# 2-LCD_CAMERA.net
KiCad netlist of a schematic drawn in Altium Designer
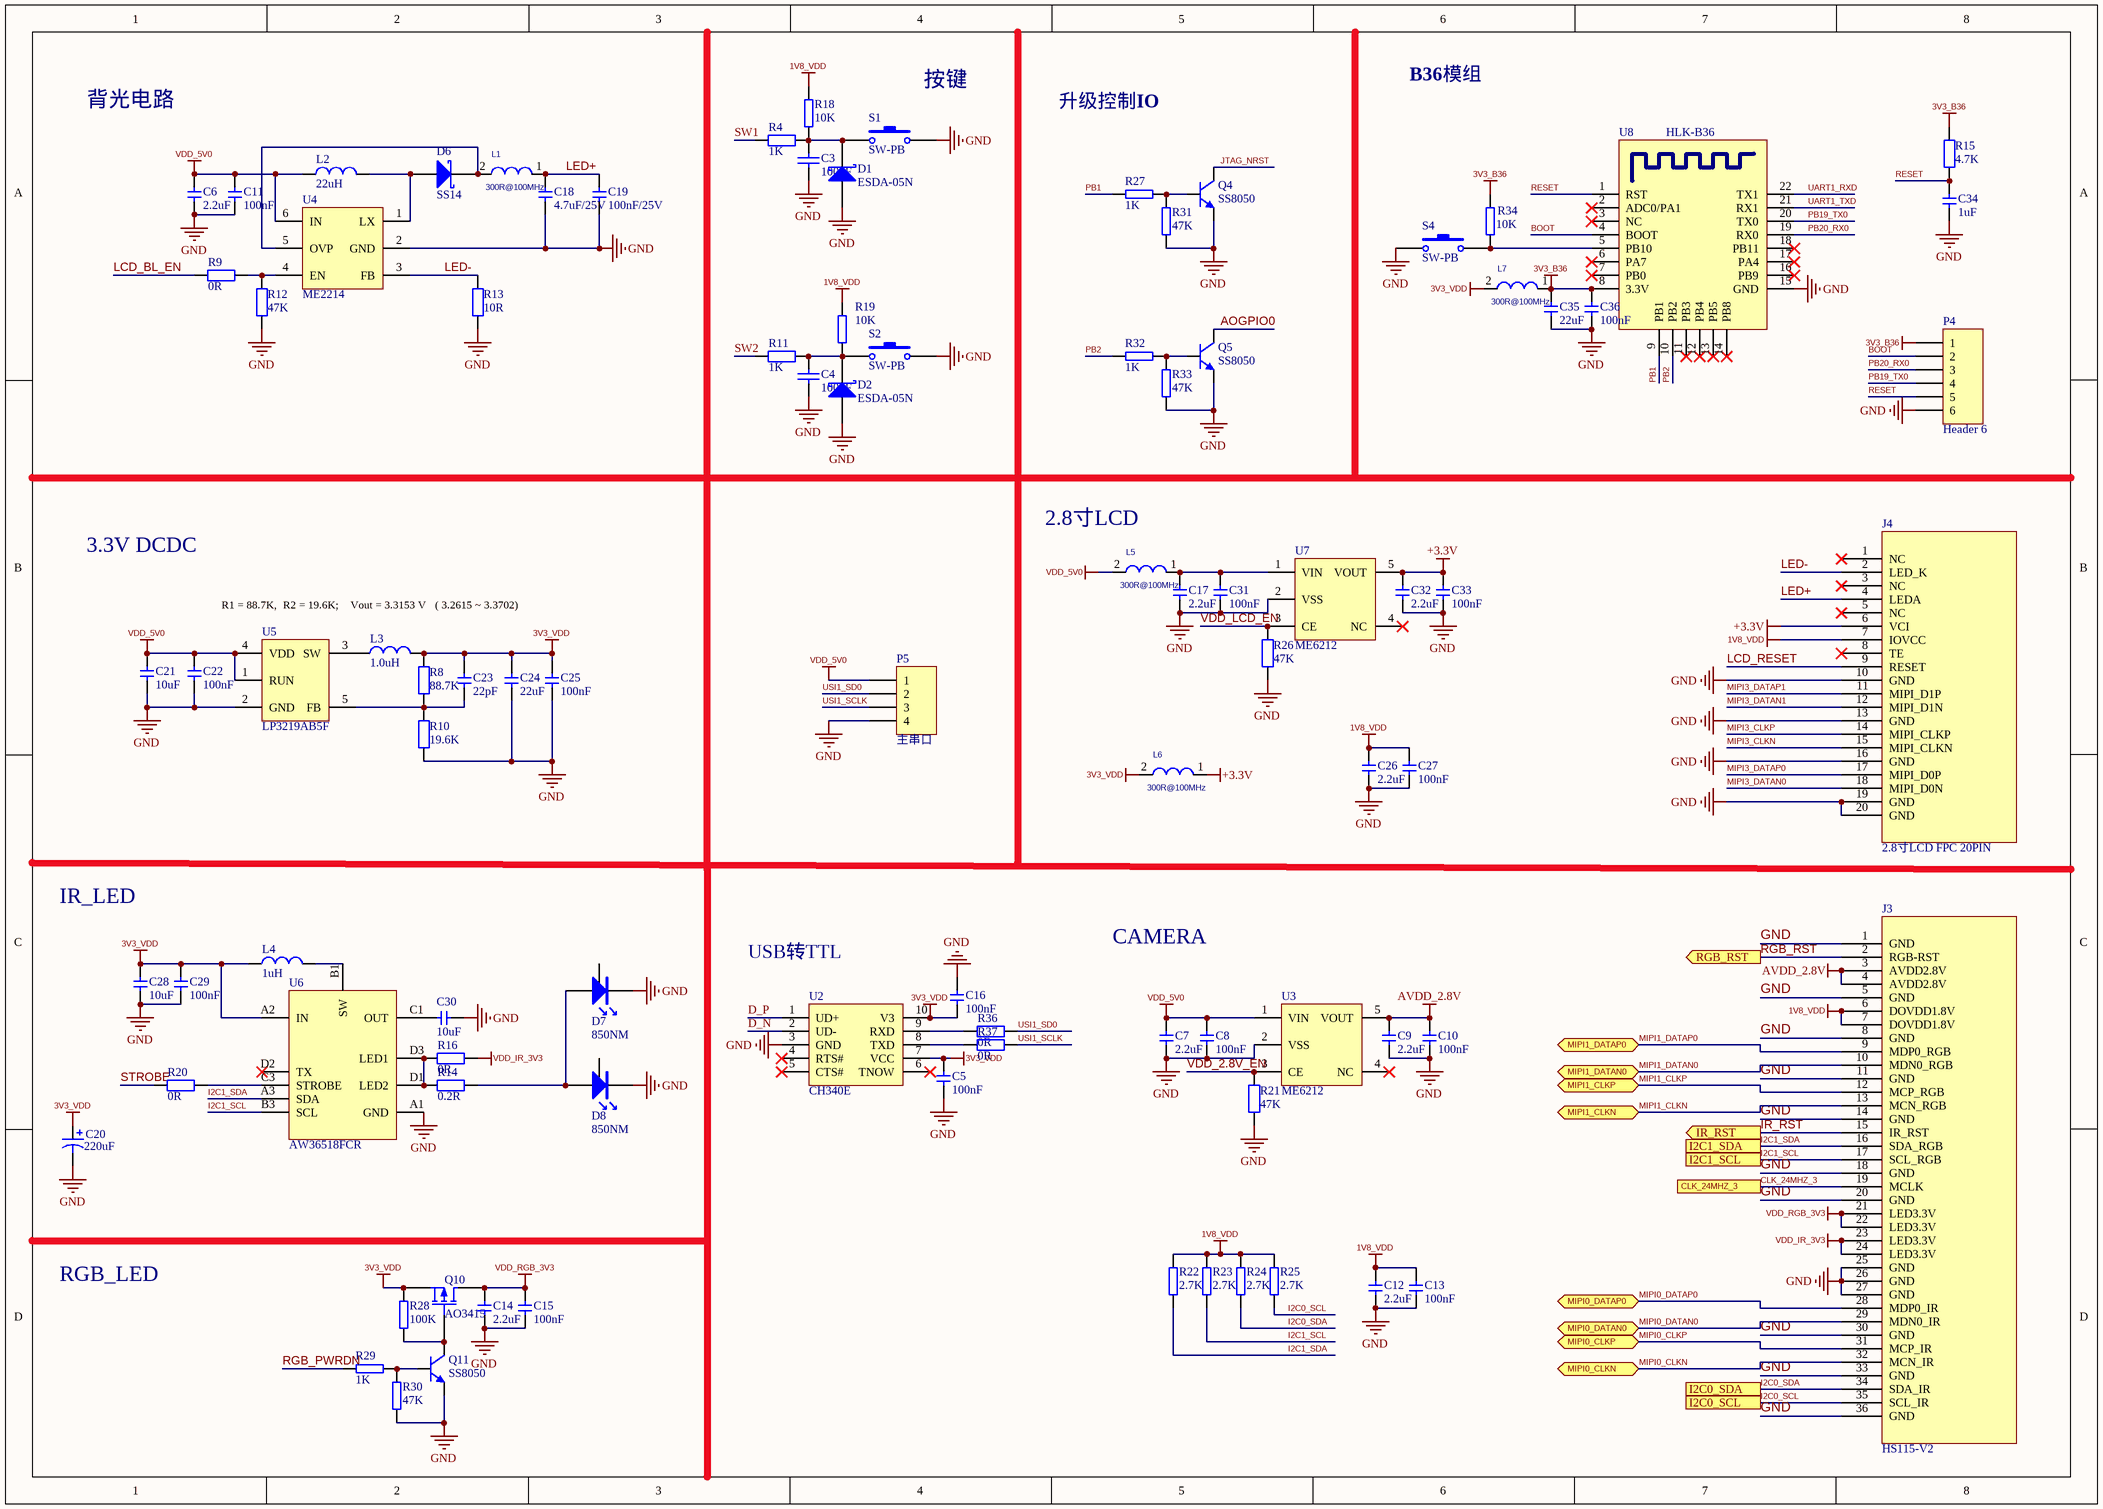
[diagram p0: 2-LCD&CAMERA.SchDoc]

(export (version "E")
  (design (tool "Eeschema 10.0.6"))
  (components
    (comp (ref "C3")
      (value "100nF")
      (footprint "C0402")
      (description "Capacitor")
      (libsource (lib "LORATEMPSENSOR_V0.02") (part "Cap"))
    )
    (comp (ref "C4")
      (value "100nF")
      (footprint "C0402")
      (description "Capacitor")
      (libsource (lib "LORATEMPSENSOR_V0.02") (part "Cap"))
    )
    (comp (ref "C5")
      (value "100nF")
      (footprint "C0402")
      (description "C?")
      (libsource (lib "HNCY_SCH_Lib") (part "CAP1"))
    )
    (comp (ref "C6")
      (value "2.2uF")
      (footprint "C0402")
      (description "C?")
      (libsource (lib "HNCY_SCH_Lib") (part "CAP1"))
    )
    (comp (ref "C7")
      (value "2.2uF")
      (footprint "C0402")
      (description "C?")
      (libsource (lib "HNCY_SCH_Lib") (part "CAP1"))
    )
    (comp (ref "C8")
      (value "100nF")
      (footprint "C0402")
      (description "C?")
      (libsource (lib "HNCY_SCH_Lib") (part "CAP1"))
    )
    (comp (ref "C9")
      (value "2.2uF")
      (footprint "C0402")
      (description "C?")
      (libsource (lib "HNCY_SCH_Lib") (part "CAP1"))
    )
    (comp (ref "C10")
      (value "100nF")
      (footprint "C0402")
      (description "C?")
      (libsource (lib "HNCY_SCH_Lib") (part "CAP1"))
    )
    (comp (ref "C11")
      (value "100nF")
      (footprint "C0402")
      (description "C?")
      (libsource (lib "HNCY_SCH_Lib") (part "CAP1"))
    )
    (comp (ref "C12")
      (value "2.2uF")
      (footprint "C0402")
      (description "C?")
      (libsource (lib "HNCY_SCH_Lib") (part "CAP1"))
    )
    (comp (ref "C13")
      (value "100nF")
      (footprint "C0402")
      (description "C?")
      (libsource (lib "HNCY_SCH_Lib") (part "CAP1"))
    )
    (comp (ref "C14")
      (value "2.2uF")
      (footprint "C0402")
      (description "C?")
      (libsource (lib "HNCY_SCH_Lib") (part "CAP1"))
    )
    (comp (ref "C15")
      (value "100nF")
      (footprint "C0402")
      (description "C?")
      (libsource (lib "HNCY_SCH_Lib") (part "CAP1"))
    )
    (comp (ref "C16")
      (value "100nF")
      (footprint "C0402")
      (description "C?")
      (libsource (lib "HNCY_SCH_Lib") (part "CAP1"))
    )
    (comp (ref "C17")
      (value "2.2uF")
      (footprint "C0402")
      (description "C?")
      (libsource (lib "HNCY_SCH_Lib") (part "CAP1"))
    )
    (comp (ref "C18")
      (value "4.7uF/25V")
      (footprint "Cap_0603")
      (description "C?")
      (libsource (lib "HNCY_SCH_Lib") (part "CAP1"))
    )
    (comp (ref "C19")
      (value "100nF/25V")
      (footprint "C0402")
      (description "C?")
      (libsource (lib "HNCY_SCH_Lib") (part "CAP1"))
    )
    (comp (ref "C20")
      (value "220uF")
      (footprint "SMD,6.3x7.7mm")
      (description "Polarized Capacitor (Radial)")
      (fields (field (name "Comment") "Cap Pol1") (field (name "PUBLISHER") "Altium Limited"))
      (libsource (lib "Miscellaneous Devices") (part "Cap Pol1"))
    )
    (comp (ref "C21")
      (value "10uF")
      (footprint "Cap_0603")
      (description "C?")
      (libsource (lib "HNCY_SCH_Lib") (part "CAP1"))
    )
    (comp (ref "C22")
      (value "100nF")
      (footprint "C0402")
      (description "C?")
      (libsource (lib "HNCY_SCH_Lib") (part "CAP1"))
    )
    (comp (ref "C23")
      (value "22pF")
      (footprint "C0402")
      (description "C?")
      (libsource (lib "HNCY_SCH_Lib") (part "CAP1"))
    )
    (comp (ref "C24")
      (value "22uF")
      (footprint "CAP_0603")
      (description "C?")
      (libsource (lib "HNCY_SCH_Lib") (part "CAP1"))
    )
    (comp (ref "C25")
      (value "100nF")
      (footprint "C0402")
      (description "C?")
      (libsource (lib "HNCY_SCH_Lib") (part "CAP1"))
    )
    (comp (ref "C26")
      (value "2.2uF")
      (footprint "C0402")
      (description "C?")
      (libsource (lib "HNCY_SCH_Lib") (part "CAP1"))
    )
    (comp (ref "C27")
      (value "100nF")
      (footprint "C0402")
      (description "C?")
      (libsource (lib "HNCY_SCH_Lib") (part "CAP1"))
    )
    (comp (ref "C28")
      (value "10uF")
      (footprint "C0402")
      (description "C?")
      (libsource (lib "HNCY_SCH_Lib") (part "CAP1"))
    )
    (comp (ref "C29")
      (value "100nF")
      (footprint "C0402")
      (description "C?")
      (libsource (lib "HNCY_SCH_Lib") (part "CAP1"))
    )
    (comp (ref "C30")
      (value "10uF")
      (footprint "C0402")
      (description "C?")
      (libsource (lib "HNCY_SCH_Lib") (part "CAP1"))
    )
    (comp (ref "C31")
      (value "100nF")
      (footprint "C0402")
      (description "C?")
      (libsource (lib "HNCY_SCH_Lib") (part "CAP1"))
    )
    (comp (ref "C32")
      (value "2.2uF")
      (footprint "C0402")
      (description "C?")
      (libsource (lib "HNCY_SCH_Lib") (part "CAP1"))
    )
    (comp (ref "C33")
      (value "100nF")
      (footprint "C0402")
      (description "C?")
      (libsource (lib "HNCY_SCH_Lib") (part "CAP1"))
    )
    (comp (ref "C34")
      (value "1uF")
      (footprint "C0402")
      (description "C?")
      (libsource (lib "HNCY_SCH_Lib") (part "CAP1"))
    )
    (comp (ref "C35")
      (value "22uF")
      (footprint "CAP_0603")
      (description "C?")
      (libsource (lib "HNCY_SCH_Lib") (part "CAP1"))
    )
    (comp (ref "C36")
      (value "100nF")
      (footprint "C0402")
      (description "C?")
      (libsource (lib "HNCY_SCH_Lib") (part "CAP1"))
    )
    (comp (ref "D1")
      (value "ESDA-05N")
      (footprint "R0402")
      (description "Silicon AF Schottky Diode for High-Speed Switching")
      (fields (field (name "PUBLISHER") "Altium Limited"))
      (libsource (lib "Miscellaneous Devices") (part "Diode BAS70"))
    )
    (comp (ref "D2")
      (value "ESDA-05N")
      (footprint "R0402")
      (description "Silicon AF Schottky Diode for High-Speed Switching")
      (fields (field (name "PUBLISHER") "Altium Limited"))
      (libsource (lib "Miscellaneous Devices") (part "Diode BAS70"))
    )
    (comp (ref "D6")
      (value "SS14")
      (footprint "SOD-123F")
      (description "Silicon AF Schottky Diode for High-Speed Switching")
      (fields (field (name "PUBLISHER") "Altium Limited"))
      (libsource (lib "Miscellaneous Devices") (part "Diode BAS70"))
    )
    (comp (ref "D7")
      (value "850NM")
      (footprint "LED-3535-850MM")
      (description "贴片LED，3535，红外850NM")
      (libsource (lib "MY SCHLIB") (part "LED_IR"))
    )
    (comp (ref "D8")
      (value "850NM")
      (footprint "LED-3535-850MM")
      (description "贴片LED，3535，红外850NM")
      (libsource (lib "Common") (part "LED_IR"))
    )
    (comp (ref "J3")
      (value "HS115-V2")
      (footprint "0.5-36PIN")
      (libsource (lib "MY SCHLIB") (part "HS115-V2"))
    )
    (comp (ref "J4")
      (value "2.8寸LCD FPC 20PIN")
      (footprint "0.5-20PIN-抽屉上接")
      (description "1-Lane MIPI")
      (libsource (lib "MY SCHLIB") (part "2.8寸LCD FPC 20PIN"))
    )
    (comp (ref "L1") (value "300R@100MHz") (footprint "Res_0603") (libsource (lib "*") (part "L/0402")))
    (comp (ref "L2") (value "22uH") (footprint "L3*3") (libsource (lib "封装") (part "LineInductors")))
    (comp (ref "L3")
      (value "1.0uH")
      (footprint "L2.5x2.0x1.0mm")
      (libsource (lib "封装") (part "LineInductors"))
    )
    (comp (ref "L4") (value "1uH") (footprint "L2.5x2.0x1.0mm") (libsource (lib "封装") (part "LineInductors")))
    (comp (ref "L5") (value "300R@100MHz") (footprint "Res_0603") (libsource (lib "*") (part "L/0402")))
    (comp (ref "L6") (value "300R@100MHz") (footprint "Res_0603") (libsource (lib "*") (part "L/0402")))
    (comp (ref "L7") (value "300R@100MHz") (footprint "Res_0603") (libsource (lib "*") (part "L/0402")))
    (comp (ref "P4")
      (value "Header 6")
      (footprint "HDR1X6")
      (description "Header, 6-Pin")
      (fields (field (name "PUBLISHER") "Altium Limited"))
      (libsource (lib "Miscellaneous Connectors") (part "Header 6"))
    )
    (comp (ref "P5")
      (value "主串口")
      (footprint "4P_2.5MM")
      (description "Header, 4-Pin")
      (fields (field (name "PUBLISHER") "Altium Limited"))
      (libsource (lib "Miscellaneous Connectors") (part "Header 4"))
    )
    (comp (ref "Q4")
      (value "SS8050")
      (footprint "SOT23-BEC")
      (description "贴片三极管")
      (libsource (lib "HNCY_SCH_Lib") (part "NPN"))
    )
    (comp (ref "Q5")
      (value "SS8050")
      (footprint "SOT23-BEC")
      (description "贴片三极管")
      (libsource (lib "HNCY_SCH_Lib") (part "NPN"))
    )
    (comp (ref "Q10") (value "AO3415") (footprint "SOT-23") (libsource (lib "*") (part "AO3415")))
    (comp (ref "Q11")
      (value "SS8050")
      (footprint "SOT23-BEC")
      (description "贴片三极管")
      (libsource (lib "HNCY_SCH_Lib") (part "NPN"))
    )
    (comp (ref "R4")
      (value "1K")
      (footprint "R0402")
      (description "Resistor")
      (fields (field (name "PUBLISHER") "Altium Limited"))
      (libsource (lib "") (part "Res2_1"))
    )
    (comp (ref "R8")
      (value "88.7K")
      (footprint "R0402")
      (description "Resistor")
      (fields (field (name "PUBLISHER") "Altium Limited"))
      (libsource (lib "Miscellaneous Devices") (part "Res2"))
    )
    (comp (ref "R9")
      (value "0R")
      (footprint "R0402")
      (description "Resistor")
      (fields (field (name "PUBLISHER") "Altium Limited"))
      (libsource (lib "") (part "Res2_1"))
    )
    (comp (ref "R10")
      (value "19.6K")
      (footprint "R0402")
      (description "Resistor")
      (fields (field (name "PUBLISHER") "Altium Limited"))
      (libsource (lib "") (part "Res2_3"))
    )
    (comp (ref "R11")
      (value "1K")
      (footprint "R0402")
      (description "Resistor")
      (fields (field (name "PUBLISHER") "Altium Limited"))
      (libsource (lib "") (part "Res2_1"))
    )
    (comp (ref "R12")
      (value "47K")
      (footprint "R0402")
      (description "Resistor")
      (fields (field (name "PUBLISHER") "Altium Limited"))
      (libsource (lib "Miscellaneous Devices") (part "Res2"))
    )
    (comp (ref "R13")
      (value "10R")
      (footprint "R0805")
      (description "Resistor")
      (fields (field (name "PUBLISHER") "Altium Limited"))
      (libsource (lib "") (part "Res2_3"))
    )
    (comp (ref "R14")
      (value "0.2R")
      (footprint "R0805")
      (description "Resistor")
      (fields (field (name "PUBLISHER") "Altium Limited"))
      (libsource (lib "") (part "Res2_1"))
    )
    (comp (ref "R15")
      (value "4.7K")
      (footprint "R0402")
      (description "Resistor")
      (fields (field (name "PUBLISHER") "Altium Limited"))
      (libsource (lib "") (part "Res2_3"))
    )
    (comp (ref "R16")
      (value "0R")
      (footprint "R0805")
      (description "Resistor")
      (fields (field (name "PUBLISHER") "Altium Limited"))
      (libsource (lib "") (part "Res2_1"))
    )
    (comp (ref "R18")
      (value "10K")
      (footprint "R0402")
      (description "R?")
      (libsource (lib "HNCY_SCH_Lib") (part "RES1"))
    )
    (comp (ref "R19")
      (value "10K")
      (footprint "R0402")
      (description "R?")
      (libsource (lib "HNCY_SCH_Lib") (part "RES1"))
    )
    (comp (ref "R20")
      (value "0R")
      (footprint "R0402")
      (description "Resistor")
      (fields (field (name "PUBLISHER") "Altium Limited"))
      (libsource (lib "") (part "Res2_1"))
    )
    (comp (ref "R21")
      (value "47K")
      (footprint "R0402")
      (description "Resistor")
      (fields (field (name "PUBLISHER") "Altium Limited"))
      (libsource (lib "Miscellaneous Devices") (part "Res2"))
    )
    (comp (ref "R22")
      (value "2.7K")
      (footprint "R0402")
      (description "R?")
      (libsource (lib "HNCY_SCH_Lib") (part "RES1"))
    )
    (comp (ref "R23")
      (value "2.7K")
      (footprint "R0402")
      (description "R?")
      (libsource (lib "HNCY_SCH_Lib") (part "RES1"))
    )
    (comp (ref "R24")
      (value "2.7K")
      (footprint "R0402")
      (description "R?")
      (libsource (lib "HNCY_SCH_Lib") (part "RES1"))
    )
    (comp (ref "R25")
      (value "2.7K")
      (footprint "R0402")
      (description "R?")
      (libsource (lib "HNCY_SCH_Lib") (part "RES1"))
    )
    (comp (ref "R26")
      (value "47K")
      (footprint "R0402")
      (description "Resistor")
      (fields (field (name "PUBLISHER") "Altium Limited"))
      (libsource (lib "Miscellaneous Devices") (part "Res2"))
    )
    (comp (ref "R27")
      (value "1K")
      (footprint "R0402")
      (description "R?")
      (libsource (lib "HNCY_SCH_Lib") (part "RES1"))
    )
    (comp (ref "R28")
      (value "100K")
      (footprint "R0402")
      (description "R?")
      (libsource (lib "HNCY_SCH_Lib") (part "RES1"))
    )
    (comp (ref "R29")
      (value "1K")
      (footprint "R0402")
      (description "R?")
      (libsource (lib "HNCY_SCH_Lib") (part "RES1"))
    )
    (comp (ref "R30")
      (value "47K")
      (footprint "R0402")
      (description "R?")
      (libsource (lib "HNCY_SCH_Lib") (part "RES1"))
    )
    (comp (ref "R31")
      (value "47K")
      (footprint "R0402")
      (description "R?")
      (libsource (lib "HNCY_SCH_Lib") (part "RES1"))
    )
    (comp (ref "R32")
      (value "1K")
      (footprint "R0402")
      (description "R?")
      (libsource (lib "HNCY_SCH_Lib") (part "RES1"))
    )
    (comp (ref "R33")
      (value "47K")
      (footprint "R0402")
      (description "R?")
      (libsource (lib "HNCY_SCH_Lib") (part "RES1"))
    )
    (comp (ref "R34")
      (value "10K")
      (footprint "R0402")
      (description "R?")
      (libsource (lib "HNCY_SCH_Lib") (part "RES1"))
    )
    (comp (ref "R36")
      (value "0R")
      (footprint "R0402")
      (description "Resistor")
      (fields (field (name "PUBLISHER") "Altium Limited"))
      (libsource (lib "") (part "Res2_2"))
    )
    (comp (ref "R37")
      (value "0R")
      (footprint "R0402")
      (description "Resistor")
      (fields (field (name "PUBLISHER") "Altium Limited"))
      (libsource (lib "") (part "Res2_2"))
    )
    (comp (ref "S1")
      (value "SW-PB")
      (footprint "轻触开关4.5x4.5")
      (description "Switch")
      (fields (field (name "PUBLISHER") "Altium Limited"))
      (libsource (lib "Miscellaneous Devices") (part "SW-PB"))
    )
    (comp (ref "S2")
      (value "SW-PB")
      (footprint "轻触开关4.5x4.5")
      (description "Switch")
      (fields (field (name "PUBLISHER") "Altium Limited"))
      (libsource (lib "Miscellaneous Devices") (part "SW-PB"))
    )
    (comp (ref "S4")
      (value "SW-PB")
      (footprint "轻触开关4.5x4.5")
      (description "Switch")
      (fields (field (name "PUBLISHER") "Altium Limited"))
      (libsource (lib "Miscellaneous Devices") (part "SW-PB"))
    )
    (comp (ref "U2") (value "CH340E") (footprint "MSOP-10") (libsource (lib "MY SCHLIB") (part "CH340E")))
    (comp (ref "U3") (value "ME6212") (footprint "SOT23-5") (libsource (lib "MY SCHLIB") (part "ME6212")))
    (comp (ref "U4") (value "ME2214") (footprint "SOT26") (libsource (lib "MY SCHLIB") (part "ME2214")))
    (comp (ref "U5") (value "LP3219AB5F") (footprint "SOT23-5") (libsource (lib "MY SCHLIB") (part "TD6817")))
    (comp (ref "U6")
      (value "AW36518FCR")
      (footprint "FCQFN-10L")
      (libsource (lib "MY SCHLIB") (part "AW36518FCR"))
    )
    (comp (ref "U7") (value "ME6212") (footprint "SOT23-5") (libsource (lib "MY SCHLIB") (part "ME6212")))
    (comp (ref "U8") (value "HLK-B36") (footprint "HLK-B36") (libsource (lib "MY SCHLIB") (part "HLK-B36")))
  )
  (nets
    (net (code "1") (name "+3.3V") (class "Default")
      (node (ref "C32") (pin "1") (pintype "passive"))
      (node (ref "C33") (pin "1") (pintype "passive"))
      (node (ref "J4") (pin "6") (pinfunction "VCI_6") (pintype "passive"))
      (node (ref "L6") (pin "1") (pinfunction "1_1") (pintype "passive"))
      (node (ref "U7") (pin "5") (pinfunction "VOUT_5") (pintype "passive"))
    )
    (net (code "2") (name "/AOGPIO0") (class "Default")
      (node (ref "Q5") (pin "C") (pinfunction "C_C") (pintype "passive"))
    )
    (net (code "3") (name "/BOOT") (class "Default")
      (node (ref "P4") (pin "2") (pinfunction "2_2") (pintype "passive"))
      (node (ref "U8") (pin "4") (pinfunction "BOOT_4") (pintype "passive"))
    )
    (net (code "4") (name "/CLK_24MHZ_3") (class "Default")
      (node (ref "J3") (pin "19") (pinfunction "MCLK_19") (pintype "passive"))
    )
    (net (code "5") (name "/D_N") (class "Default")
      (node (ref "U2") (pin "2") (pinfunction "UD-_2") (pintype "passive"))
    )
    (net (code "6") (name "/D_P") (class "Default")
      (node (ref "U2") (pin "1") (pinfunction "UD+_1") (pintype "passive"))
    )
    (net (code "7") (name "/I2C0_SCL") (class "Default")
      (node (ref "J3") (pin "35") (pinfunction "SCL_IR_35") (pintype "passive"))
      (node (ref "R25") (pin "2") (pinfunction "2_2") (pintype "passive"))
    )
    (net (code "8") (name "/I2C0_SDA") (class "Default")
      (node (ref "J3") (pin "34") (pinfunction "SDA_IR_34") (pintype "passive"))
      (node (ref "R24") (pin "2") (pinfunction "2_2") (pintype "passive"))
    )
    (net (code "9") (name "/I2C1_SCL") (class "Default")
      (node (ref "J3") (pin "17") (pinfunction "SCL_RGB_17") (pintype "passive"))
      (node (ref "R23") (pin "2") (pinfunction "2_2") (pintype "passive"))
      (node (ref "U6") (pin "B3") (pinfunction "SCL_B3") (pintype "passive"))
    )
    (net (code "10") (name "/I2C1_SDA") (class "Default")
      (node (ref "J3") (pin "16") (pinfunction "SDA_RGB_16") (pintype "passive"))
      (node (ref "R22") (pin "2") (pinfunction "2_2") (pintype "passive"))
      (node (ref "U6") (pin "A3") (pinfunction "SDA_A3") (pintype "passive"))
    )
    (net (code "11") (name "/IR_RST") (class "Default")
      (node (ref "J3") (pin "15") (pinfunction "IR_RST_15") (pintype "passive"))
    )
    (net (code "12") (name "/JTAG_NRST") (class "Default")
      (node (ref "Q4") (pin "C") (pinfunction "C_C") (pintype "passive"))
    )
    (net (code "13") (name "/LCD_BL_EN") (class "Default")
      (node (ref "R9") (pin "1") (pinfunction "1_1") (pintype "passive"))
    )
    (net (code "14") (name "/LCD_RESET") (class "Default")
      (node (ref "J4") (pin "9") (pinfunction "RESET_9") (pintype "passive"))
    )
    (net (code "15") (name "/LED+") (class "Default")
      (node (ref "C18") (pin "1") (pintype "passive"))
      (node (ref "C19") (pin "1") (pintype "passive"))
      (node (ref "J4") (pin "4") (pinfunction "LEDA_4") (pintype "passive"))
      (node (ref "L1") (pin "1") (pinfunction "1_1") (pintype "passive"))
    )
    (net (code "16") (name "/LED-") (class "Default")
      (node (ref "J4") (pin "2") (pinfunction "LED_K_2") (pintype "passive"))
      (node (ref "R13") (pin "1") (pinfunction "1_1") (pintype "passive"))
      (node (ref "U4") (pin "3") (pinfunction "FB_3") (pintype "passive"))
    )
    (net (code "17") (name "/MIPI0_CLKN") (class "Default")
      (node (ref "J3") (pin "32") (pinfunction "MCN_IR_32") (pintype "passive"))
    )
    (net (code "18") (name "/MIPI0_CLKP") (class "Default")
      (node (ref "J3") (pin "31") (pinfunction "MCP_IR_31") (pintype "passive"))
    )
    (net (code "19") (name "/MIPI0_DATAN0") (class "Default")
      (node (ref "J3") (pin "29") (pinfunction "MDN0_IR_29") (pintype "passive"))
    )
    (net (code "20") (name "/MIPI0_DATAP0") (class "Default")
      (node (ref "J3") (pin "28") (pinfunction "MDP0_IR_28") (pintype "passive"))
    )
    (net (code "21") (name "/MIPI1_CLKN") (class "Default")
      (node (ref "J3") (pin "13") (pinfunction "MCN_RGB_13") (pintype "passive"))
    )
    (net (code "22") (name "/MIPI1_CLKP") (class "Default")
      (node (ref "J3") (pin "12") (pinfunction "MCP_RGB_12") (pintype "passive"))
    )
    (net (code "23") (name "/MIPI1_DATAN0") (class "Default")
      (node (ref "J3") (pin "10") (pinfunction "MDN0_RGB_10") (pintype "passive"))
    )
    (net (code "24") (name "/MIPI1_DATAP0") (class "Default")
      (node (ref "J3") (pin "9") (pinfunction "MDP0_RGB_9") (pintype "passive"))
    )
    (net (code "25") (name "/MIPI3_CLKN") (class "Default")
      (node (ref "J4") (pin "15") (pinfunction "MIPI_CLKN_15") (pintype "passive"))
    )
    (net (code "26") (name "/MIPI3_CLKP") (class "Default")
      (node (ref "J4") (pin "14") (pinfunction "MIPI_CLKP_14") (pintype "passive"))
    )
    (net (code "27") (name "/MIPI3_DATAN0") (class "Default")
      (node (ref "J4") (pin "18") (pinfunction "MIPI_D0N_18") (pintype "passive"))
    )
    (net (code "28") (name "/MIPI3_DATAN1") (class "Default")
      (node (ref "J4") (pin "12") (pinfunction "MIPI_D1N_12") (pintype "passive"))
    )
    (net (code "29") (name "/MIPI3_DATAP0") (class "Default")
      (node (ref "J4") (pin "17") (pinfunction "MIPI_D0P_17") (pintype "passive"))
    )
    (net (code "30") (name "/MIPI3_DATAP1") (class "Default")
      (node (ref "J4") (pin "11") (pinfunction "MIPI_D1P_11") (pintype "passive"))
    )
    (net (code "31") (name "/PB1") (class "Default")
      (node (ref "R27") (pin "2") (pinfunction "2_2") (pintype "passive"))
      (node (ref "U8") (pin "9") (pinfunction "PB1_9") (pintype "passive"))
    )
    (net (code "32") (name "/PB2") (class "Default")
      (node (ref "R32") (pin "2") (pinfunction "2_2") (pintype "passive"))
      (node (ref "U8") (pin "10") (pinfunction "PB2_10") (pintype "passive"))
    )
    (net (code "33") (name "/PB19_TX0") (class "Default")
      (node (ref "P4") (pin "4") (pinfunction "4_4") (pintype "passive"))
      (node (ref "U8") (pin "20") (pinfunction "TX0_20") (pintype "passive"))
    )
    (net (code "34") (name "/PB20_RX0") (class "Default")
      (node (ref "P4") (pin "3") (pinfunction "3_3") (pintype "passive"))
      (node (ref "U8") (pin "19") (pinfunction "RX0_19") (pintype "passive"))
    )
    (net (code "35") (name "/RESET") (class "Default")
      (node (ref "C34") (pin "1") (pintype "passive"))
      (node (ref "P4") (pin "5") (pinfunction "5_5") (pintype "passive"))
      (node (ref "R15") (pin "2") (pinfunction "2_2") (pintype "passive"))
      (node (ref "U8") (pin "1") (pinfunction "RST_1") (pintype "passive"))
    )
    (net (code "36") (name "/RGB_PWRDN") (class "Default")
      (node (ref "R29") (pin "2") (pinfunction "2_2") (pintype "passive"))
    )
    (net (code "37") (name "/RGB_RST") (class "Default")
      (node (ref "J3") (pin "2") (pinfunction "RGB-RST_2") (pintype "passive"))
    )
    (net (code "38") (name "/STROBE") (class "Default")
      (node (ref "R20") (pin "1") (pinfunction "1_1") (pintype "passive"))
    )
    (net (code "39") (name "/SW1") (class "Default")
      (node (ref "R4") (pin "1") (pinfunction "1_1") (pintype "passive"))
    )
    (net (code "40") (name "/SW2") (class "Default")
      (node (ref "R11") (pin "1") (pinfunction "1_1") (pintype "passive"))
    )
    (net (code "41") (name "/UART1_RXD") (class "Default")
      (node (ref "U8") (pin "22") (pinfunction "TX1_22") (pintype "passive"))
    )
    (net (code "42") (name "/UART1_TXD") (class "Default")
      (node (ref "U8") (pin "21") (pinfunction "RX1_21") (pintype "passive"))
    )
    (net (code "43") (name "/USI1_SCLK") (class "Default")
      (node (ref "P5") (pin "3") (pinfunction "3_3") (pintype "passive"))
      (node (ref "R37") (pin "1") (pinfunction "1_1") (pintype "passive"))
    )
    (net (code "44") (name "/USI1_SD0") (class "Default")
      (node (ref "P5") (pin "2") (pinfunction "2_2") (pintype "passive"))
      (node (ref "R36") (pin "1") (pinfunction "1_1") (pintype "passive"))
    )
    (net (code "45") (name "/VDD_2.8V_EN") (class "Default")
      (node (ref "R21") (pin "2") (pinfunction "2_2") (pintype "passive"))
      (node (ref "U3") (pin "3") (pinfunction "CE_3") (pintype "passive"))
    )
    (net (code "46") (name "/VDD_LCD_EN") (class "Default")
      (node (ref "R26") (pin "2") (pinfunction "2_2") (pintype "passive"))
      (node (ref "U7") (pin "3") (pinfunction "CE_3") (pintype "passive"))
    )
    (net (code "47") (name "1V8_VDD") (class "Default")
      (node (ref "C12") (pin "1") (pintype "passive"))
      (node (ref "C13") (pin "1") (pintype "passive"))
      (node (ref "C26") (pin "1") (pintype "passive"))
      (node (ref "C27") (pin "1") (pintype "passive"))
      (node (ref "J3") (pin "6") (pinfunction "DOVDD1.8V_6") (pintype "passive"))
      (node (ref "J3") (pin "7") (pinfunction "DOVDD1.8V_7") (pintype "passive"))
      (node (ref "J4") (pin "7") (pinfunction "IOVCC_7") (pintype "passive"))
      (node (ref "R18") (pin "2") (pinfunction "2_2") (pintype "passive"))
      (node (ref "R19") (pin "2") (pinfunction "2_2") (pintype "passive"))
      (node (ref "R22") (pin "1") (pinfunction "1_1") (pintype "passive"))
      (node (ref "R23") (pin "1") (pinfunction "1_1") (pintype "passive"))
      (node (ref "R24") (pin "1") (pinfunction "1_1") (pintype "passive"))
      (node (ref "R25") (pin "1") (pinfunction "1_1") (pintype "passive"))
    )
    (net (code "48") (name "3V3_B36") (class "Default")
      (node (ref "C35") (pin "1") (pintype "passive"))
      (node (ref "C36") (pin "1") (pintype "passive"))
      (node (ref "L7") (pin "1") (pinfunction "1_1") (pintype "passive"))
      (node (ref "P4") (pin "1") (pinfunction "1_1") (pintype "passive"))
      (node (ref "R15") (pin "1") (pinfunction "1_1") (pintype "passive"))
      (node (ref "R34") (pin "2") (pinfunction "2_2") (pintype "passive"))
      (node (ref "U8") (pin "8") (pinfunction "3.3V_8") (pintype "passive"))
    )
    (net (code "49") (name "3V3_VDD") (class "Default")
      (node (ref "C16") (pin "1") (pintype "passive"))
      (node (ref "C20") (pin "1") (pinfunction "1_1") (pintype "passive"))
      (node (ref "C23") (pin "2") (pintype "passive"))
      (node (ref "C24") (pin "1") (pintype "passive"))
      (node (ref "C25") (pin "1") (pintype "passive"))
      (node (ref "C28") (pin "1") (pintype "passive"))
      (node (ref "C29") (pin "1") (pintype "passive"))
      (node (ref "C5") (pin "2") (pintype "passive"))
      (node (ref "L3") (pin "2") (pinfunction "2_2") (pintype "passive"))
      (node (ref "L4") (pin "1") (pinfunction "1_1") (pintype "passive"))
      (node (ref "L6") (pin "2") (pinfunction "2_2") (pintype "passive"))
      (node (ref "L7") (pin "2") (pinfunction "2_2") (pintype "passive"))
      (node (ref "Q10") (pin "2") (pinfunction "S_2") (pintype "passive"))
      (node (ref "R28") (pin "2") (pinfunction "2_2") (pintype "passive"))
      (node (ref "R8") (pin "2") (pinfunction "2_2") (pintype "passive"))
      (node (ref "U2") (pin "10") (pinfunction "V3_10") (pintype "passive"))
      (node (ref "U2") (pin "7") (pinfunction "VCC_7") (pintype "passive"))
      (node (ref "U6") (pin "A2") (pinfunction "IN_A2") (pintype "passive"))
    )
    (net (code "50") (name "AVDD_2.8V") (class "Default")
      (node (ref "C10") (pin "1") (pintype "passive"))
      (node (ref "C9") (pin "1") (pintype "passive"))
      (node (ref "J3") (pin "3") (pinfunction "AVDD2.8V_3") (pintype "passive"))
      (node (ref "J3") (pin "4") (pinfunction "AVDD2.8V_4") (pintype "passive"))
      (node (ref "U3") (pin "5") (pinfunction "VOUT_5") (pintype "passive"))
    )
    (net (code "51") (name "GND") (class "Default")
      (node (ref "C10") (pin "2") (pintype "passive"))
      (node (ref "C11") (pin "2") (pintype "passive"))
      (node (ref "C12") (pin "2") (pintype "passive"))
      (node (ref "C13") (pin "2") (pintype "passive"))
      (node (ref "C14") (pin "2") (pintype "passive"))
      (node (ref "C15") (pin "2") (pintype "passive"))
      (node (ref "C16") (pin "2") (pintype "passive"))
      (node (ref "C17") (pin "2") (pintype "passive"))
      (node (ref "C18") (pin "2") (pintype "passive"))
      (node (ref "C19") (pin "2") (pintype "passive"))
      (node (ref "C20") (pin "2") (pinfunction "2_2") (pintype "passive"))
      (node (ref "C21") (pin "2") (pintype "passive"))
      (node (ref "C22") (pin "2") (pintype "passive"))
      (node (ref "C24") (pin "2") (pintype "passive"))
      (node (ref "C25") (pin "2") (pintype "passive"))
      (node (ref "C26") (pin "2") (pintype "passive"))
      (node (ref "C27") (pin "2") (pintype "passive"))
      (node (ref "C28") (pin "2") (pintype "passive"))
      (node (ref "C29") (pin "2") (pintype "passive"))
      (node (ref "C3") (pin "2") (pinfunction "2_2") (pintype "passive"))
      (node (ref "C30") (pin "2") (pintype "passive"))
      (node (ref "C31") (pin "2") (pintype "passive"))
      (node (ref "C32") (pin "2") (pintype "passive"))
      (node (ref "C33") (pin "2") (pintype "passive"))
      (node (ref "C34") (pin "2") (pintype "passive"))
      (node (ref "C35") (pin "2") (pintype "passive"))
      (node (ref "C36") (pin "2") (pintype "passive"))
      (node (ref "C4") (pin "2") (pinfunction "2_2") (pintype "passive"))
      (node (ref "C5") (pin "1") (pintype "passive"))
      (node (ref "C6") (pin "2") (pintype "passive"))
      (node (ref "C7") (pin "2") (pintype "passive"))
      (node (ref "C8") (pin "2") (pintype "passive"))
      (node (ref "C9") (pin "2") (pintype "passive"))
      (node (ref "D1") (pin "1") (pinfunction "A_1") (pintype "passive"))
      (node (ref "D2") (pin "1") (pinfunction "A_1") (pintype "passive"))
      (node (ref "D7") (pin "K") (pinfunction "K_K") (pintype "passive"))
      (node (ref "D8") (pin "K") (pinfunction "K_K") (pintype "passive"))
      (node (ref "J3") (pin "1") (pinfunction "GND_1") (pintype "passive"))
      (node (ref "J3") (pin "11") (pinfunction "GND_11") (pintype "passive"))
      (node (ref "J3") (pin "14") (pinfunction "GND_14") (pintype "passive"))
      (node (ref "J3") (pin "18") (pinfunction "GND_18") (pintype "passive"))
      (node (ref "J3") (pin "20") (pinfunction "GND_20") (pintype "passive"))
      (node (ref "J3") (pin "25") (pinfunction "GND_25") (pintype "passive"))
      (node (ref "J3") (pin "26") (pinfunction "GND_26") (pintype "passive"))
      (node (ref "J3") (pin "27") (pinfunction "GND_27") (pintype "passive"))
      (node (ref "J3") (pin "30") (pinfunction "GND_30") (pintype "passive"))
      (node (ref "J3") (pin "33") (pinfunction "GND_33") (pintype "passive"))
      (node (ref "J3") (pin "36") (pinfunction "GND_36") (pintype "passive"))
      (node (ref "J3") (pin "5") (pinfunction "GND_5") (pintype "passive"))
      (node (ref "J3") (pin "8") (pinfunction "GND_8") (pintype "passive"))
      (node (ref "J4") (pin "10") (pinfunction "GND_10") (pintype "passive"))
      (node (ref "J4") (pin "13") (pinfunction "GND_13") (pintype "passive"))
      (node (ref "J4") (pin "16") (pinfunction "GND_16") (pintype "passive"))
      (node (ref "J4") (pin "19") (pinfunction "GND_19") (pintype "passive"))
      (node (ref "J4") (pin "20") (pinfunction "GND_20") (pintype "passive"))
      (node (ref "P4") (pin "6") (pinfunction "6_6") (pintype "passive"))
      (node (ref "P5") (pin "4") (pinfunction "4_4") (pintype "passive"))
      (node (ref "Q11") (pin "E") (pinfunction "E_E") (pintype "passive"))
      (node (ref "Q4") (pin "E") (pinfunction "E_E") (pintype "passive"))
      (node (ref "Q5") (pin "E") (pinfunction "E_E") (pintype "passive"))
      (node (ref "R10") (pin "2") (pinfunction "2_2") (pintype "passive"))
      (node (ref "R12") (pin "1") (pinfunction "1_1") (pintype "passive"))
      (node (ref "R13") (pin "2") (pinfunction "2_2") (pintype "passive"))
      (node (ref "R21") (pin "1") (pinfunction "1_1") (pintype "passive"))
      (node (ref "R26") (pin "1") (pinfunction "1_1") (pintype "passive"))
      (node (ref "R30") (pin "2") (pinfunction "2_2") (pintype "passive"))
      (node (ref "R31") (pin "2") (pinfunction "2_2") (pintype "passive"))
      (node (ref "R33") (pin "2") (pinfunction "2_2") (pintype "passive"))
      (node (ref "S1") (pin "2") (pinfunction "2_2") (pintype "passive"))
      (node (ref "S2") (pin "2") (pinfunction "2_2") (pintype "passive"))
      (node (ref "S4") (pin "1") (pinfunction "1_1") (pintype "passive"))
      (node (ref "U2") (pin "3") (pinfunction "GND_3") (pintype "passive"))
      (node (ref "U3") (pin "2") (pinfunction "VSS_2") (pintype "passive"))
      (node (ref "U4") (pin "2") (pinfunction "GND_2") (pintype "passive"))
      (node (ref "U5") (pin "2") (pinfunction "GND_2") (pintype "passive"))
      (node (ref "U6") (pin "A1") (pinfunction "GND_A1") (pintype "passive"))
      (node (ref "U7") (pin "2") (pinfunction "VSS_2") (pintype "passive"))
      (node (ref "U8") (pin "15") (pinfunction "GND_15") (pintype "passive"))
    )
    (net (code "52") (name "Net-(D1-K)") (class "Default")
      (node (ref "C3") (pin "1") (pinfunction "1_1") (pintype "passive"))
      (node (ref "D1") (pin "2") (pinfunction "K_2") (pintype "passive"))
      (node (ref "R18") (pin "1") (pinfunction "1_1") (pintype "passive"))
      (node (ref "R4") (pin "2") (pinfunction "2_2") (pintype "passive"))
      (node (ref "S1") (pin "1") (pinfunction "1_1") (pintype "passive"))
    )
    (net (code "53") (name "Net-(D2-K)") (class "Default")
      (node (ref "C4") (pin "1") (pinfunction "1_1") (pintype "passive"))
      (node (ref "D2") (pin "2") (pinfunction "K_2") (pintype "passive"))
      (node (ref "R11") (pin "2") (pinfunction "2_2") (pintype "passive"))
      (node (ref "R19") (pin "1") (pinfunction "1_1") (pintype "passive"))
      (node (ref "S2") (pin "1") (pinfunction "1_1") (pintype "passive"))
    )
    (net (code "54") (name "Net-(D6-A)") (class "Default")
      (node (ref "D6") (pin "1") (pinfunction "A_1") (pintype "passive"))
      (node (ref "L2") (pin "2") (pinfunction "2_2") (pintype "passive"))
      (node (ref "U4") (pin "1") (pinfunction "LX_1") (pintype "passive"))
    )
    (net (code "55") (name "Net-(D6-K)") (class "Default")
      (node (ref "D6") (pin "2") (pinfunction "K_2") (pintype "passive"))
      (node (ref "L1") (pin "2") (pinfunction "2_2") (pintype "passive"))
      (node (ref "U4") (pin "5") (pinfunction "OVP_5") (pintype "passive"))
    )
    (net (code "56") (name "Net-(D7-PadA)") (class "Default")
      (node (ref "D7") (pin "A") (pinfunction "A_A") (pintype "passive"))
      (node (ref "D8") (pin "A") (pinfunction "A_A") (pintype "passive"))
      (node (ref "R14") (pin "2") (pinfunction "2_2") (pintype "passive"))
    )
    (net (code "57") (name "Net-(Q4-PadB)") (class "Default")
      (node (ref "Q4") (pin "B") (pinfunction "B_B") (pintype "passive"))
      (node (ref "R27") (pin "1") (pinfunction "1_1") (pintype "passive"))
      (node (ref "R31") (pin "1") (pinfunction "1_1") (pintype "passive"))
    )
    (net (code "58") (name "Net-(Q5-PadB)") (class "Default")
      (node (ref "Q5") (pin "B") (pinfunction "B_B") (pintype "passive"))
      (node (ref "R32") (pin "1") (pinfunction "1_1") (pintype "passive"))
      (node (ref "R33") (pin "1") (pinfunction "1_1") (pintype "passive"))
    )
    (net (code "59") (name "Net-(Q10-G)") (class "Default")
      (node (ref "Q10") (pin "1") (pinfunction "G_1") (pintype "passive"))
      (node (ref "Q11") (pin "C") (pinfunction "C_C") (pintype "passive"))
      (node (ref "R28") (pin "1") (pinfunction "1_1") (pintype "passive"))
    )
    (net (code "60") (name "Net-(Q11-PadB)") (class "Default")
      (node (ref "Q11") (pin "B") (pinfunction "B_B") (pintype "passive"))
      (node (ref "R29") (pin "1") (pinfunction "1_1") (pintype "passive"))
      (node (ref "R30") (pin "1") (pinfunction "1_1") (pintype "passive"))
    )
    (net (code "61") (name "Net-(U2-RXD)") (class "Default")
      (node (ref "R36") (pin "2") (pinfunction "2_2") (pintype "passive"))
      (node (ref "U2") (pin "9") (pinfunction "RXD_9") (pintype "passive"))
    )
    (net (code "62") (name "Net-(U2-TXD)") (class "Default")
      (node (ref "R37") (pin "2") (pinfunction "2_2") (pintype "passive"))
      (node (ref "U2") (pin "8") (pinfunction "TXD_8") (pintype "passive"))
    )
    (net (code "63") (name "Net-(U4-EN)") (class "Default")
      (node (ref "R12") (pin "2") (pinfunction "2_2") (pintype "passive"))
      (node (ref "R9") (pin "2") (pinfunction "2_2") (pintype "passive"))
      (node (ref "U4") (pin "4") (pinfunction "EN_4") (pintype "passive"))
    )
    (net (code "64") (name "Net-(U5-FB)") (class "Default")
      (node (ref "C23") (pin "1") (pintype "passive"))
      (node (ref "R10") (pin "1") (pinfunction "1_1") (pintype "passive"))
      (node (ref "R8") (pin "1") (pinfunction "1_1") (pintype "passive"))
      (node (ref "U5") (pin "5") (pinfunction "FB_5") (pintype "passive"))
    )
    (net (code "65") (name "Net-(U5-SW)") (class "Default")
      (node (ref "L3") (pin "1") (pinfunction "1_1") (pintype "passive"))
      (node (ref "U5") (pin "3") (pinfunction "SW_3") (pintype "passive"))
    )
    (net (code "66") (name "Net-(U6-LED1)") (class "Default")
      (node (ref "R14") (pin "1") (pinfunction "1_1") (pintype "passive"))
      (node (ref "R16") (pin "1") (pinfunction "1_1") (pintype "passive"))
      (node (ref "U6") (pin "D1") (pinfunction "LED2_D1") (pintype "passive"))
      (node (ref "U6") (pin "D3") (pinfunction "LED1_D3") (pintype "passive"))
    )
    (net (code "67") (name "Net-(U6-OUT)") (class "Default")
      (node (ref "C30") (pin "1") (pintype "passive"))
      (node (ref "U6") (pin "C1") (pinfunction "OUT_C1") (pintype "passive"))
    )
    (net (code "68") (name "Net-(U6-STROBE)") (class "Default")
      (node (ref "R20") (pin "2") (pinfunction "2_2") (pintype "passive"))
      (node (ref "U6") (pin "C3") (pinfunction "STROBE_C3") (pintype "passive"))
    )
    (net (code "69") (name "Net-(U6-SW)") (class "Default")
      (node (ref "L4") (pin "2") (pinfunction "2_2") (pintype "passive"))
      (node (ref "U6") (pin "B1") (pinfunction "SW_B1") (pintype "passive"))
    )
    (net (code "70") (name "Net-(U7-VIN)") (class "Default")
      (node (ref "C17") (pin "1") (pintype "passive"))
      (node (ref "C31") (pin "1") (pintype "passive"))
      (node (ref "L5") (pin "1") (pinfunction "1_1") (pintype "passive"))
      (node (ref "U7") (pin "1") (pinfunction "VIN_1") (pintype "passive"))
    )
    (net (code "71") (name "Net-(U8-PB10)") (class "Default")
      (node (ref "R34") (pin "1") (pinfunction "1_1") (pintype "passive"))
      (node (ref "S4") (pin "2") (pinfunction "2_2") (pintype "passive"))
      (node (ref "U8") (pin "5") (pinfunction "PB10_5") (pintype "passive"))
    )
    (net (code "72") (name "VDD_5V0") (class "Default")
      (node (ref "C11") (pin "1") (pintype "passive"))
      (node (ref "C21") (pin "1") (pintype "passive"))
      (node (ref "C22") (pin "1") (pintype "passive"))
      (node (ref "C6") (pin "1") (pintype "passive"))
      (node (ref "C7") (pin "1") (pintype "passive"))
      (node (ref "C8") (pin "1") (pintype "passive"))
      (node (ref "L2") (pin "1") (pinfunction "1_1") (pintype "passive"))
      (node (ref "L5") (pin "2") (pinfunction "2_2") (pintype "passive"))
      (node (ref "P5") (pin "1") (pinfunction "1_1") (pintype "passive"))
      (node (ref "U3") (pin "1") (pinfunction "VIN_1") (pintype "passive"))
      (node (ref "U4") (pin "6") (pinfunction "IN_6") (pintype "passive"))
      (node (ref "U5") (pin "1") (pinfunction "RUN_1") (pintype "passive"))
      (node (ref "U5") (pin "4") (pinfunction "VDD_4") (pintype "passive"))
    )
    (net (code "73") (name "VDD_IR_3V3") (class "Default")
      (node (ref "J3") (pin "23") (pinfunction "LED3.3V_23") (pintype "passive"))
      (node (ref "J3") (pin "24") (pinfunction "LED3.3V_24") (pintype "passive"))
      (node (ref "R16") (pin "2") (pinfunction "2_2") (pintype "passive"))
    )
    (net (code "74") (name "VDD_RGB_3V3") (class "Default")
      (node (ref "C14") (pin "1") (pintype "passive"))
      (node (ref "C15") (pin "1") (pintype "passive"))
      (node (ref "J3") (pin "21") (pinfunction "LED3.3V_21") (pintype "passive"))
      (node (ref "J3") (pin "22") (pinfunction "LED3.3V_22") (pintype "passive"))
      (node (ref "Q10") (pin "3") (pinfunction "D_3") (pintype "passive"))
    )
    (net (code "75") (name "unconnected-(D7-Pad0)") (class "Default")
      (node (ref "D7") (pin "0") (pinfunction "0_0") (pintype "passive"))
    )
    (net (code "76") (name "unconnected-(D8-Pad0)") (class "Default")
      (node (ref "D8") (pin "0") (pinfunction "0_0") (pintype "passive"))
    )
    (net (code "77") (name "unconnected-(J4-NC-Pad1)") (class "Default")
      (node (ref "J4") (pin "1") (pinfunction "NC_1") (pintype "passive+no_connect"))
    )
    (net (code "78") (name "unconnected-(J4-NC-Pad3)") (class "Default")
      (node (ref "J4") (pin "3") (pinfunction "NC_3") (pintype "passive+no_connect"))
    )
    (net (code "79") (name "unconnected-(J4-NC-Pad5)") (class "Default")
      (node (ref "J4") (pin "5") (pinfunction "NC_5") (pintype "passive+no_connect"))
    )
    (net (code "80") (name "unconnected-(J4-TE-Pad8)") (class "Default")
      (node (ref "J4") (pin "8") (pinfunction "TE_8") (pintype "passive+no_connect"))
    )
    (net (code "81") (name "unconnected-(U2-CTS#-Pad5)") (class "Default")
      (node (ref "U2") (pin "5") (pinfunction "CTS#_5") (pintype "passive+no_connect"))
    )
    (net (code "82") (name "unconnected-(U2-RTS#-Pad4)") (class "Default")
      (node (ref "U2") (pin "4") (pinfunction "RTS#_4") (pintype "passive+no_connect"))
    )
    (net (code "83") (name "unconnected-(U2-TNOW-Pad6)") (class "Default")
      (node (ref "U2") (pin "6") (pinfunction "TNOW_6") (pintype "passive+no_connect"))
    )
    (net (code "84") (name "unconnected-(U3-NC-Pad4)") (class "Default")
      (node (ref "U3") (pin "4") (pinfunction "NC_4") (pintype "passive+no_connect"))
    )
    (net (code "85") (name "unconnected-(U6-TX-PadD2)") (class "Default")
      (node (ref "U6") (pin "D2") (pinfunction "TX_D2") (pintype "passive+no_connect"))
    )
    (net (code "86") (name "unconnected-(U7-NC-Pad4)") (class "Default")
      (node (ref "U7") (pin "4") (pinfunction "NC_4") (pintype "passive+no_connect"))
    )
    (net (code "87") (name "unconnected-(U8-ADC0{slash}PA1-Pad2)") (class "Default")
      (node (ref "U8") (pin "2") (pinfunction "ADC0/PA1_2") (pintype "passive+no_connect"))
    )
    (net (code "88") (name "unconnected-(U8-NC-Pad3)") (class "Default")
      (node (ref "U8") (pin "3") (pinfunction "NC_3") (pintype "passive+no_connect"))
    )
    (net (code "89") (name "unconnected-(U8-PA4-Pad17)") (class "Default")
      (node (ref "U8") (pin "17") (pinfunction "PA4_17") (pintype "passive+no_connect"))
    )
    (net (code "90") (name "unconnected-(U8-PA7-Pad6)") (class "Default")
      (node (ref "U8") (pin "6") (pinfunction "PA7_6") (pintype "passive+no_connect"))
    )
    (net (code "91") (name "unconnected-(U8-PB0-Pad7)") (class "Default")
      (node (ref "U8") (pin "7") (pinfunction "PB0_7") (pintype "passive+no_connect"))
    )
    (net (code "92") (name "unconnected-(U8-PB3-Pad11)") (class "Default")
      (node (ref "U8") (pin "11") (pinfunction "PB3_11") (pintype "passive+no_connect"))
    )
    (net (code "93") (name "unconnected-(U8-PB4-Pad12)") (class "Default")
      (node (ref "U8") (pin "12") (pinfunction "PB4_12") (pintype "passive+no_connect"))
    )
    (net (code "94") (name "unconnected-(U8-PB5-Pad13)") (class "Default")
      (node (ref "U8") (pin "13") (pinfunction "PB5_13") (pintype "passive+no_connect"))
    )
    (net (code "95") (name "unconnected-(U8-PB8-Pad14)") (class "Default")
      (node (ref "U8") (pin "14") (pinfunction "PB8_14") (pintype "passive+no_connect"))
    )
    (net (code "96") (name "unconnected-(U8-PB9-Pad16)") (class "Default")
      (node (ref "U8") (pin "16") (pinfunction "PB9_16") (pintype "passive+no_connect"))
    )
    (net (code "97") (name "unconnected-(U8-PB11-Pad18)") (class "Default")
      (node (ref "U8") (pin "18") (pinfunction "PB11_18") (pintype "passive+no_connect"))
    )
  )
)
